# 5.net
KiCad netlist of a schematic drawn in Altium Designer
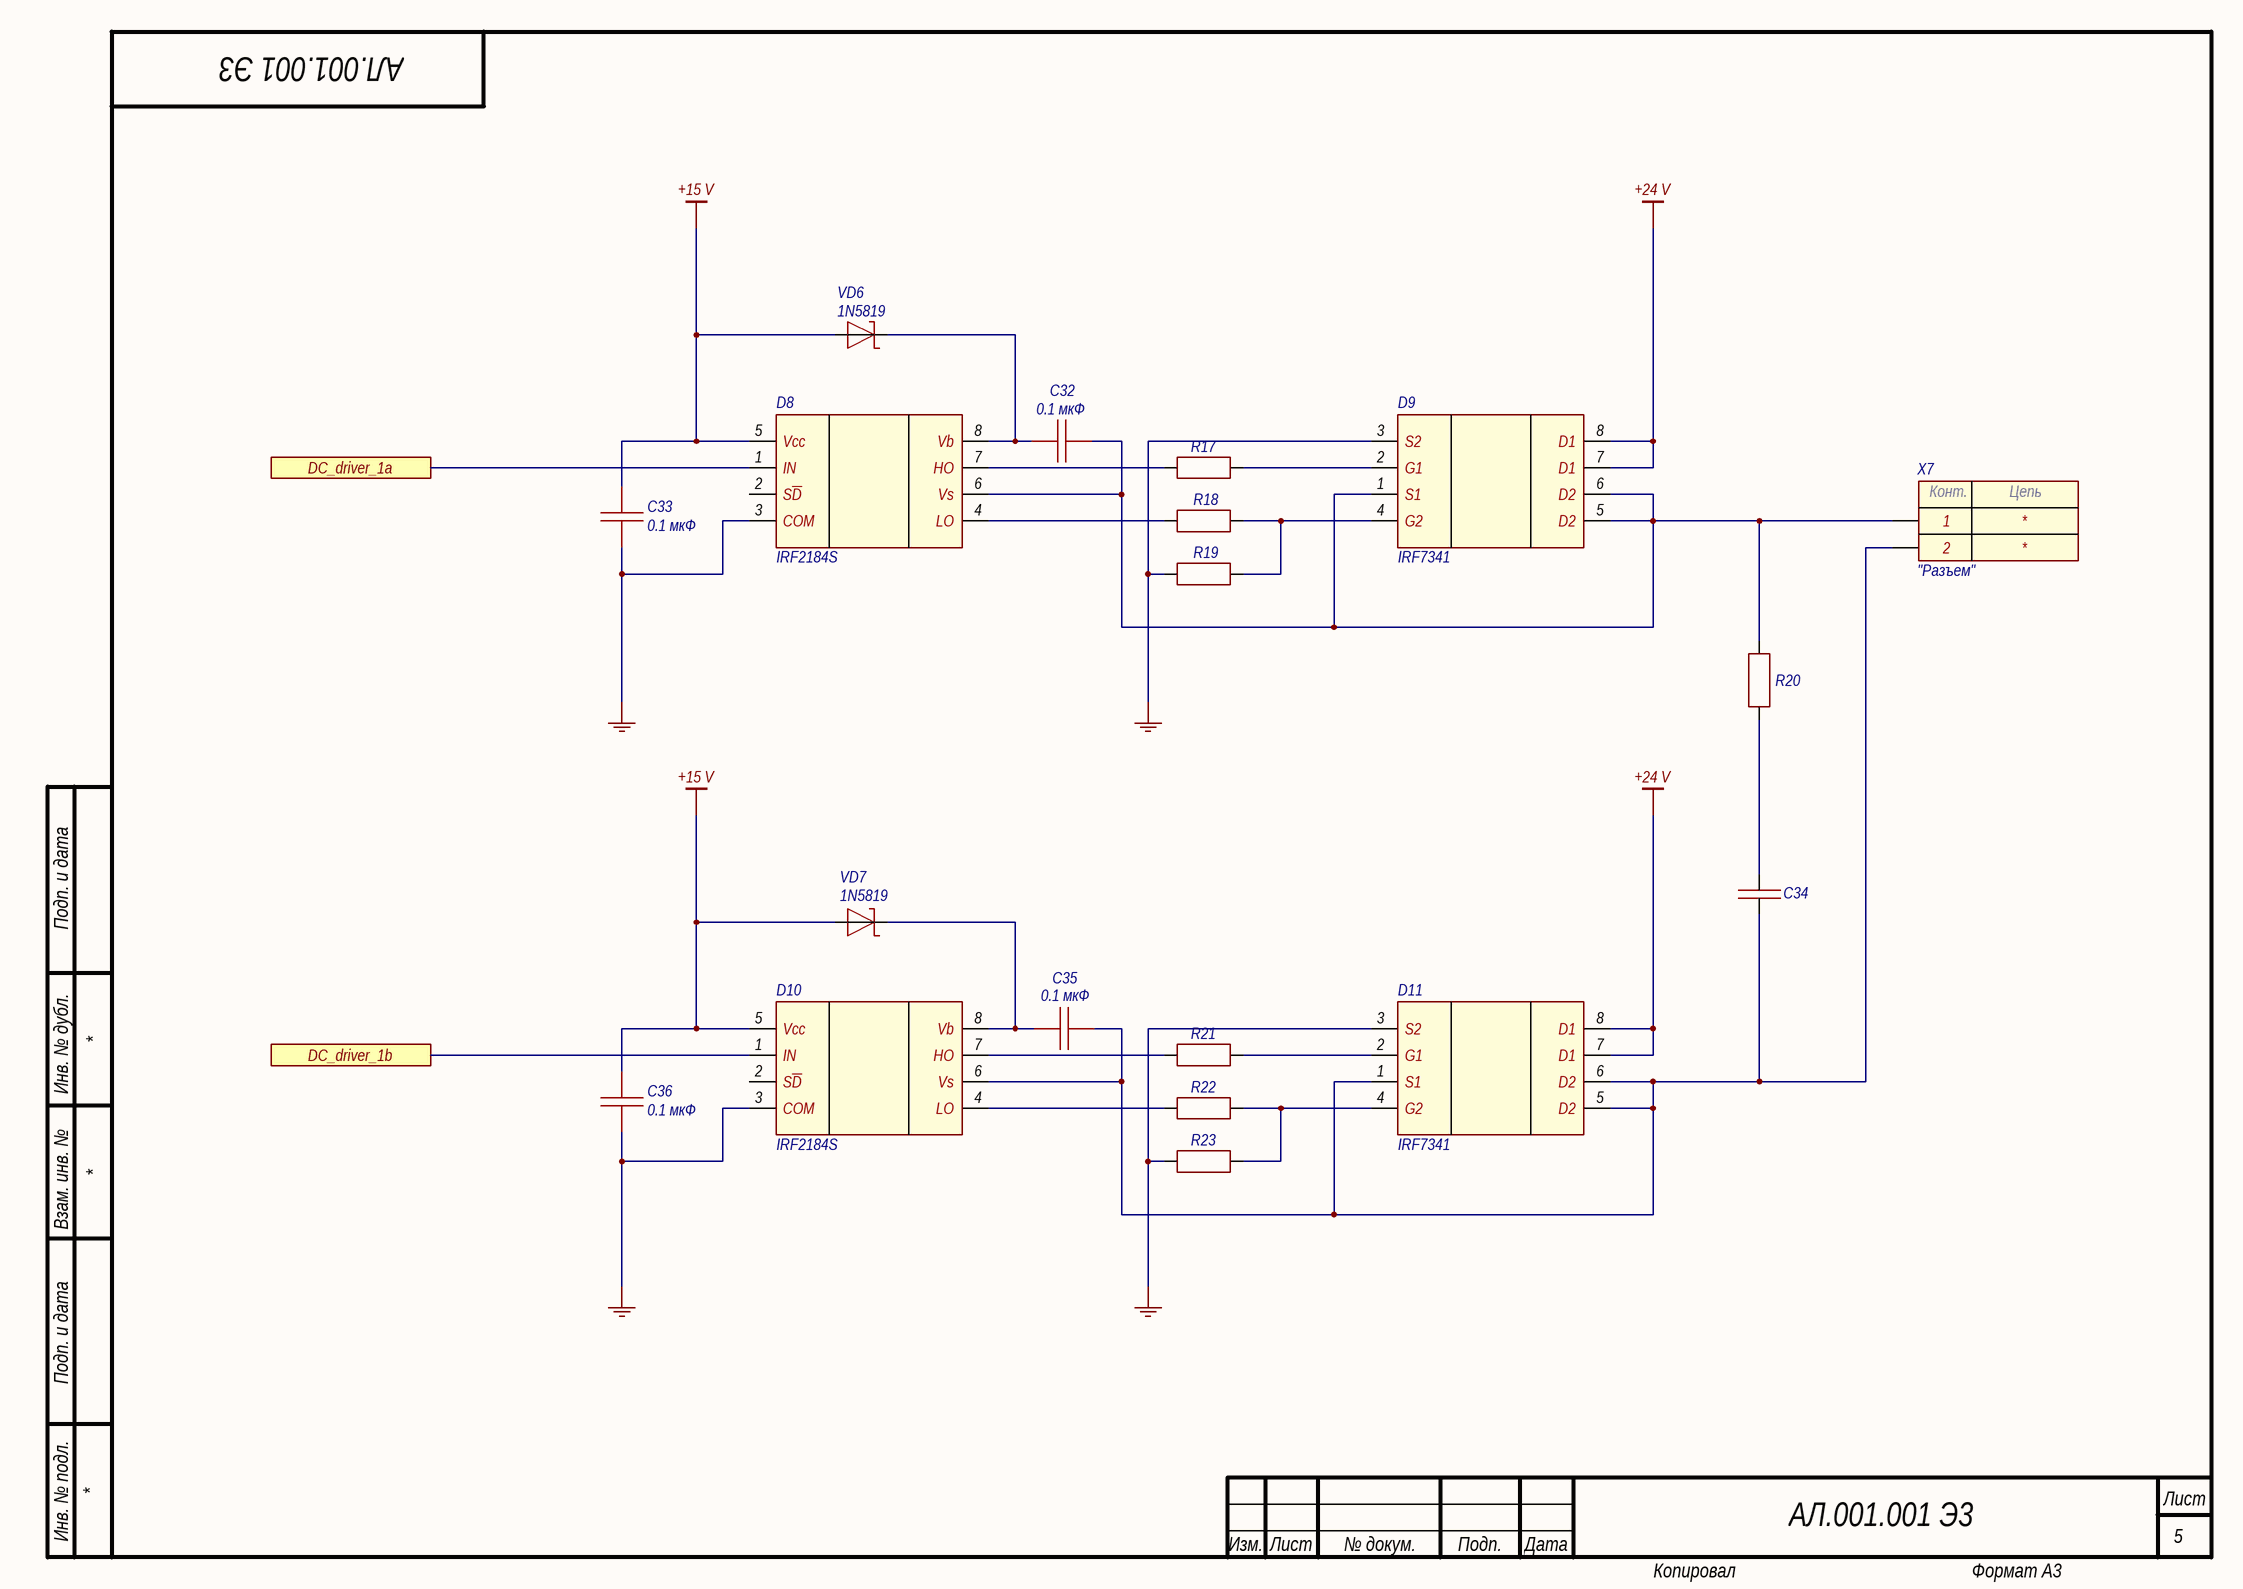
[diagram p0: Лист 5.SchDoc]

(export (version "E")
  (design (tool "Eeschema 10.0.6"))
  (components
    (comp (ref "C32")
      (value "0.1 мкФ")
      (footprint "StandardCase:CAP: 1210")
      (fields
        (field (name "MANUFACTURER") "Yageo")
        (field (name "PARTNUMBER") "CC1210KKX7R9BB104")
        (field (name "VALUEMANUFACTURERPARTNUMBER") "Ceramic capacitor, 0.1 мкФ, X7R, ±10%, 50V, 1210, -55...+125°C")
      )
      (libsource (lib "Capacitor") (part "Ceramic_1210"))
    )
    (comp (ref "C33")
      (value "0.1 мкФ")
      (footprint "StandardCase:CAP: 1210")
      (fields
        (field (name "MANUFACTURER") "Yageo")
        (field (name "PARTNUMBER") "CC1210KKX7R9BB104")
        (field (name "VALUEMANUFACTURERPARTNUMBER") "Ceramic capacitor, 0.1 мкФ, X7R, ±10%, 50V, 1210, -55...+125°C")
      )
      (libsource (lib "Capacitor") (part "Ceramic_1210"))
    )
    (comp (ref "C34")
      (value "~")
      (footprint "StandardCase:CAP: 0805")
      (fields
        (field (name "MANUFACTURER") "Yageo")
        (field (name "PARTNUMBER") "CC0805KRX7R7BB104")
        (field (name "VALUEMANUFACTURERPARTNUMBER") "Ceramic capacitor, 0.1 мкФ, X7R, ±10%, 16 В, 0805, -55...+125°C")
      )
      (libsource (lib "Capacitor") (part "Ceramic_0805"))
    )
    (comp (ref "C35")
      (value "0.1 мкФ")
      (footprint "StandardCase:CAP: 1210")
      (fields
        (field (name "MANUFACTURER") "Yageo")
        (field (name "PARTNUMBER") "CC1210KKX7R9BB104")
        (field (name "VALUEMANUFACTURERPARTNUMBER") "Ceramic capacitor, 0.1 мкФ, X7R, ±10%, 50V, 1210, -55...+125°C")
      )
      (libsource (lib "Capacitor") (part "Ceramic_1210"))
    )
    (comp (ref "C36")
      (value "0.1 мкФ")
      (footprint "StandardCase:CAP: 1210")
      (fields
        (field (name "MANUFACTURER") "Yageo")
        (field (name "PARTNUMBER") "CC1210KKX7R9BB104")
        (field (name "VALUEMANUFACTURERPARTNUMBER") "Ceramic capacitor, 0.1 мкФ, X7R, ±10%, 50V, 1210, -55...+125°C")
      )
      (libsource (lib "Capacitor") (part "Ceramic_1210"))
    )
    (comp (ref "D8")
      (value "IRF2184S")
      (footprint "StandardCase:8-SOIC")
      (libsource (lib "IC") (part "IRF2184S"))
    )
    (comp (ref "D9")
      (value "IRF7341")
      (footprint "StandardCase:8-SOIC")
      (libsource (lib "IC") (part "IRF7341"))
    )
    (comp (ref "D10")
      (value "IRF2184S")
      (footprint "StandardCase:8-SOIC")
      (libsource (lib "IC") (part "IRF2184S"))
    )
    (comp (ref "D11")
      (value "IRF7341")
      (footprint "StandardCase:8-SOIC")
      (libsource (lib "IC") (part "IRF7341"))
    )
    (comp (ref "R17")
      (value "2,7 кОм")
      (footprint "StandardCase:RES: 0805")
      (fields
        (field (name "MANUFACTURER") "Yageo")
        (field (name "PARTNUMBER") "RC0805JR-07100RL")
        (field (name "VALUEMANUFACTURERPARTNUMBER") "Resistor film, 4,7 кОм, ±5%, 0805, 0.125W, -55...+125°C")
      )
      (libsource (lib "") (part "Resistor_0805_1"))
    )
    (comp (ref "R18")
      (value "2,7 кОм")
      (footprint "StandardCase:RES: 0805")
      (fields
        (field (name "MANUFACTURER") "Yageo")
        (field (name "PARTNUMBER") "RC0805JR-07100RL")
        (field (name "VALUEMANUFACTURERPARTNUMBER") "Resistor film, 4,7 кОм, ±5%, 0805, 0.125W, -55...+125°C")
      )
      (libsource (lib "") (part "Resistor_0805_1"))
    )
    (comp (ref "R19")
      (value "2,7 кОм")
      (footprint "StandardCase:RES: 0805")
      (fields
        (field (name "MANUFACTURER") "Yageo")
        (field (name "PARTNUMBER") "RC0805JR-07100RL")
        (field (name "VALUEMANUFACTURERPARTNUMBER") "Resistor film, 4,7 кОм, ±5%, 0805, 0.125W, -55...+125°C")
      )
      (libsource (lib "") (part "Resistor_0805_1"))
    )
    (comp (ref "R20")
      (value "2,7 кОм")
      (footprint "StandardCase:RES: 0805")
      (fields
        (field (name "MANUFACTURER") "Yageo")
        (field (name "PARTNUMBER") "RC0805JR-07100RL")
        (field (name "VALUEMANUFACTURERPARTNUMBER") "Resistor film, 4,7 кОм, ±5%, 0805, 0.125W, -55...+125°C")
      )
      (libsource (lib "Resistor") (part "Resistor_0805"))
    )
    (comp (ref "R21")
      (value "2,7 кОм")
      (footprint "StandardCase:RES: 0805")
      (fields
        (field (name "MANUFACTURER") "Yageo")
        (field (name "PARTNUMBER") "RC0805JR-07100RL")
        (field (name "VALUEMANUFACTURERPARTNUMBER") "Resistor film, 4,7 кОм, ±5%, 0805, 0.125W, -55...+125°C")
      )
      (libsource (lib "") (part "Resistor_0805_1"))
    )
    (comp (ref "R22")
      (value "2,7 кОм")
      (footprint "StandardCase:RES: 0805")
      (fields
        (field (name "MANUFACTURER") "Yageo")
        (field (name "PARTNUMBER") "RC0805JR-07100RL")
        (field (name "VALUEMANUFACTURERPARTNUMBER") "Resistor film, 4,7 кОм, ±5%, 0805, 0.125W, -55...+125°C")
      )
      (libsource (lib "") (part "Resistor_0805_1"))
    )
    (comp (ref "R23")
      (value "2,7 кОм")
      (footprint "StandardCase:RES: 0805")
      (fields
        (field (name "MANUFACTURER") "Yageo")
        (field (name "PARTNUMBER") "RC0805JR-07100RL")
        (field (name "VALUEMANUFACTURERPARTNUMBER") "Resistor film, 4,7 кОм, ±5%, 0805, 0.125W, -55...+125°C")
      )
      (libsource (lib "") (part "Resistor_0805_1"))
    )
    (comp (ref "VD6")
      (value "~")
      (footprint "StandardCase:DIODE: SOD123")
      (fields
        (field (name "MANUFACTURER") "Diodes Incorporated")
        (field (name "VALUEMANUFACTURERPARTNUMBER") "Schottky diode, 80V, 500mA, 1V, 15pF, SOD-123, -55...+150°C")
        (field (name "VOLTAGE") "80V")
        (field (name "PARTNUMBER") "1N5819")
      )
      (libsource (lib "Diode") (part "Schottky_single"))
    )
    (comp (ref "VD7")
      (value "~")
      (footprint "StandardCase:DIODE: SOD123")
      (fields
        (field (name "MANUFACTURER") "Diodes Incorporated")
        (field (name "VALUEMANUFACTURERPARTNUMBER") "Schottky diode, 80V, 500mA, 1V, 15pF, SOD-123, -55...+150°C")
        (field (name "VOLTAGE") "80V")
        (field (name "PARTNUMBER") "1N5819")
      )
      (libsource (lib "Diode") (part "Schottky_single"))
    )
    (comp (ref "X7")
      (value "~")
      (footprint "CustomCase:CON: CWF-2")
      (fields
        (field (name "MANUFACTURER") "Connfly")
        (field (name "VALUEMANUFACTURERPARTNUMBER") "Connector, 2pin, 2.54mm, 250VAC, 3A")
        (field (name "PARTNUMBER") "CWF-2R")
        (field (name "COMMENTTEXT") "\"Разъем\"")
      )
      (libsource (lib "Connector") (part "CWF-2R(CWF-2)"))
    )
  )
  (nets
    (net (code "1") (name "+15 V") (class "Default")
      (node (ref "C33") (pin "2") (pinfunction "2_2") (pintype "power_in"))
      (node (ref "C36") (pin "2") (pinfunction "2_2") (pintype "power_in"))
      (node (ref "D10") (pin "5") (pinfunction "Vcc_5") (pintype "passive"))
      (node (ref "D8") (pin "5") (pinfunction "Vcc_5") (pintype "passive"))
      (node (ref "VD6") (pin "1") (pinfunction "1_1") (pintype "passive"))
      (node (ref "VD7") (pin "1") (pinfunction "1_1") (pintype "passive"))
    )
    (net (code "2") (name "+24 V") (class "Default")
      (node (ref "D11") (pin "7") (pinfunction "D1_7") (pintype "passive"))
      (node (ref "D11") (pin "8") (pinfunction "D1_8") (pintype "passive"))
      (node (ref "D9") (pin "7") (pinfunction "D1_7") (pintype "passive"))
      (node (ref "D9") (pin "8") (pinfunction "D1_8") (pintype "passive"))
    )
    (net (code "3") (name "/DC_driver_1a") (class "Default")
      (node (ref "D8") (pin "1") (pinfunction "IN_1") (pintype "passive"))
    )
    (net (code "4") (name "/DC_driver_1b") (class "Default")
      (node (ref "D10") (pin "1") (pinfunction "IN_1") (pintype "passive"))
    )
    (net (code "5") (name "GND") (class "Default")
      (node (ref "C33") (pin "1") (pinfunction "1_1") (pintype "power_in"))
      (node (ref "C36") (pin "1") (pinfunction "1_1") (pintype "power_in"))
      (node (ref "D10") (pin "3") (pinfunction "COM_3") (pintype "passive"))
      (node (ref "D11") (pin "3") (pinfunction "S2_3") (pintype "passive"))
      (node (ref "D8") (pin "3") (pinfunction "COM_3") (pintype "passive"))
      (node (ref "D9") (pin "3") (pinfunction "S2_3") (pintype "passive"))
      (node (ref "R19") (pin "2") (pinfunction "2_2") (pintype "passive"))
      (node (ref "R23") (pin "2") (pinfunction "2_2") (pintype "passive"))
    )
    (net (code "6") (name "Net-(C34-Pad2)") (class "Default")
      (node (ref "C34") (pin "2") (pinfunction "2_2") (pintype "power_in"))
      (node (ref "R20") (pin "2") (pinfunction "2_2") (pintype "passive"))
    )
    (net (code "7") (name "Net-(D8-HO)") (class "Default")
      (node (ref "D8") (pin "7") (pinfunction "HO_7") (pintype "passive"))
      (node (ref "R17") (pin "2") (pinfunction "2_2") (pintype "passive"))
    )
    (net (code "8") (name "Net-(D8-LO)") (class "Default")
      (node (ref "D8") (pin "4") (pinfunction "LO_4") (pintype "passive"))
      (node (ref "R18") (pin "2") (pinfunction "2_2") (pintype "passive"))
    )
    (net (code "9") (name "Net-(D8-Vb)") (class "Default")
      (node (ref "C32") (pin "2") (pinfunction "2_2") (pintype "power_in"))
      (node (ref "D8") (pin "8") (pinfunction "Vb_8") (pintype "passive"))
      (node (ref "VD6") (pin "2") (pinfunction "2_2") (pintype "passive"))
    )
    (net (code "10") (name "Net-(D8-Vs)") (class "Default")
      (node (ref "C32") (pin "1") (pinfunction "1_1") (pintype "power_in"))
      (node (ref "D8") (pin "6") (pinfunction "Vs_6") (pintype "passive"))
      (node (ref "D9") (pin "1") (pinfunction "S1_1") (pintype "passive"))
      (node (ref "D9") (pin "5") (pinfunction "D2_5") (pintype "passive"))
      (node (ref "D9") (pin "6") (pinfunction "D2_6") (pintype "passive"))
      (node (ref "R20") (pin "1") (pinfunction "1_1") (pintype "passive"))
      (node (ref "X7") (pin "1") (pinfunction "1_1") (pintype "passive"))
    )
    (net (code "11") (name "Net-(D9-G1)") (class "Default")
      (node (ref "D9") (pin "2") (pinfunction "G1_2") (pintype "passive"))
      (node (ref "R17") (pin "1") (pinfunction "1_1") (pintype "passive"))
    )
    (net (code "12") (name "Net-(D9-G2)") (class "Default")
      (node (ref "D9") (pin "4") (pinfunction "G2_4") (pintype "passive"))
      (node (ref "R18") (pin "1") (pinfunction "1_1") (pintype "passive"))
      (node (ref "R19") (pin "1") (pinfunction "1_1") (pintype "passive"))
    )
    (net (code "13") (name "Net-(D10-HO)") (class "Default")
      (node (ref "D10") (pin "7") (pinfunction "HO_7") (pintype "passive"))
      (node (ref "R21") (pin "2") (pinfunction "2_2") (pintype "passive"))
    )
    (net (code "14") (name "Net-(D10-LO)") (class "Default")
      (node (ref "D10") (pin "4") (pinfunction "LO_4") (pintype "passive"))
      (node (ref "R22") (pin "2") (pinfunction "2_2") (pintype "passive"))
    )
    (net (code "15") (name "Net-(D10-Vb)") (class "Default")
      (node (ref "C35") (pin "2") (pinfunction "2_2") (pintype "power_in"))
      (node (ref "D10") (pin "8") (pinfunction "Vb_8") (pintype "passive"))
      (node (ref "VD7") (pin "2") (pinfunction "2_2") (pintype "passive"))
    )
    (net (code "16") (name "Net-(D10-Vs)") (class "Default")
      (node (ref "C34") (pin "1") (pinfunction "1_1") (pintype "power_in"))
      (node (ref "C35") (pin "1") (pinfunction "1_1") (pintype "power_in"))
      (node (ref "D10") (pin "6") (pinfunction "Vs_6") (pintype "passive"))
      (node (ref "D11") (pin "1") (pinfunction "S1_1") (pintype "passive"))
      (node (ref "D11") (pin "5") (pinfunction "D2_5") (pintype "passive"))
      (node (ref "D11") (pin "6") (pinfunction "D2_6") (pintype "passive"))
      (node (ref "X7") (pin "2") (pinfunction "2_2") (pintype "passive"))
    )
    (net (code "17") (name "Net-(D11-G1)") (class "Default")
      (node (ref "D11") (pin "2") (pinfunction "G1_2") (pintype "passive"))
      (node (ref "R21") (pin "1") (pinfunction "1_1") (pintype "passive"))
    )
    (net (code "18") (name "Net-(D11-G2)") (class "Default")
      (node (ref "D11") (pin "4") (pinfunction "G2_4") (pintype "passive"))
      (node (ref "R22") (pin "1") (pinfunction "1_1") (pintype "passive"))
      (node (ref "R23") (pin "1") (pinfunction "1_1") (pintype "passive"))
    )
    (net (code "19") (name "unconnected-(D8-S~{D}-Pad2)") (class "Default")
      (node (ref "D8") (pin "2") (pinfunction "S~{D}_2") (pintype "passive"))
    )
    (net (code "20") (name "unconnected-(D10-S~{D}-Pad2)") (class "Default")
      (node (ref "D10") (pin "2") (pinfunction "S~{D}_2") (pintype "passive"))
    )
  )
)
